# Color_sensor.net
KiCad netlist of a schematic drawn in Altium Designer
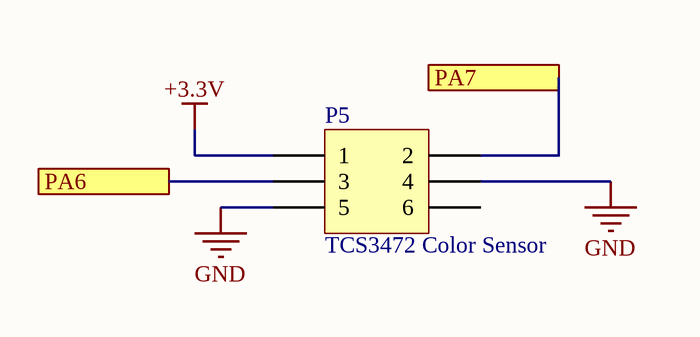
[diagram p0: Color_sensor.SchDoc]

(export (version "E")
  (design (tool "Eeschema 10.0.6"))
  (components
    (comp (ref "P5")
      (value "TCS3472 Color Sensor")
      (footprint "HDR2X3")
      (description "Header, 3-Pin, Dual row")
      (fields (field (name "PUBLISHER") "Altium Limited"))
      (libsource (lib "Miscellaneous Connectors") (part "Header 3X2"))
    )
  )
  (nets
    (net (code "1") (name "+3.3V") (class "Default")
      (node (ref "P5") (pin "1") (pinfunction "1_1") (pintype "passive"))
    )
    (net (code "2") (name "/PA6") (class "Default")
      (node (ref "P5") (pin "3") (pinfunction "3_3") (pintype "passive"))
    )
    (net (code "3") (name "/PA7") (class "Default")
      (node (ref "P5") (pin "2") (pinfunction "2_2") (pintype "passive"))
    )
    (net (code "4") (name "GND") (class "Default")
      (node (ref "P5") (pin "4") (pinfunction "4_4") (pintype "passive"))
      (node (ref "P5") (pin "5") (pinfunction "5_5") (pintype "passive"))
    )
    (net (code "5") (name "unconnected-(P5-Pad6)") (class "Default")
      (node (ref "P5") (pin "6") (pinfunction "6_6") (pintype "passive"))
    )
  )
)
